# riser-v2.net
KiCad netlist of a schematic drawn in EAGLE
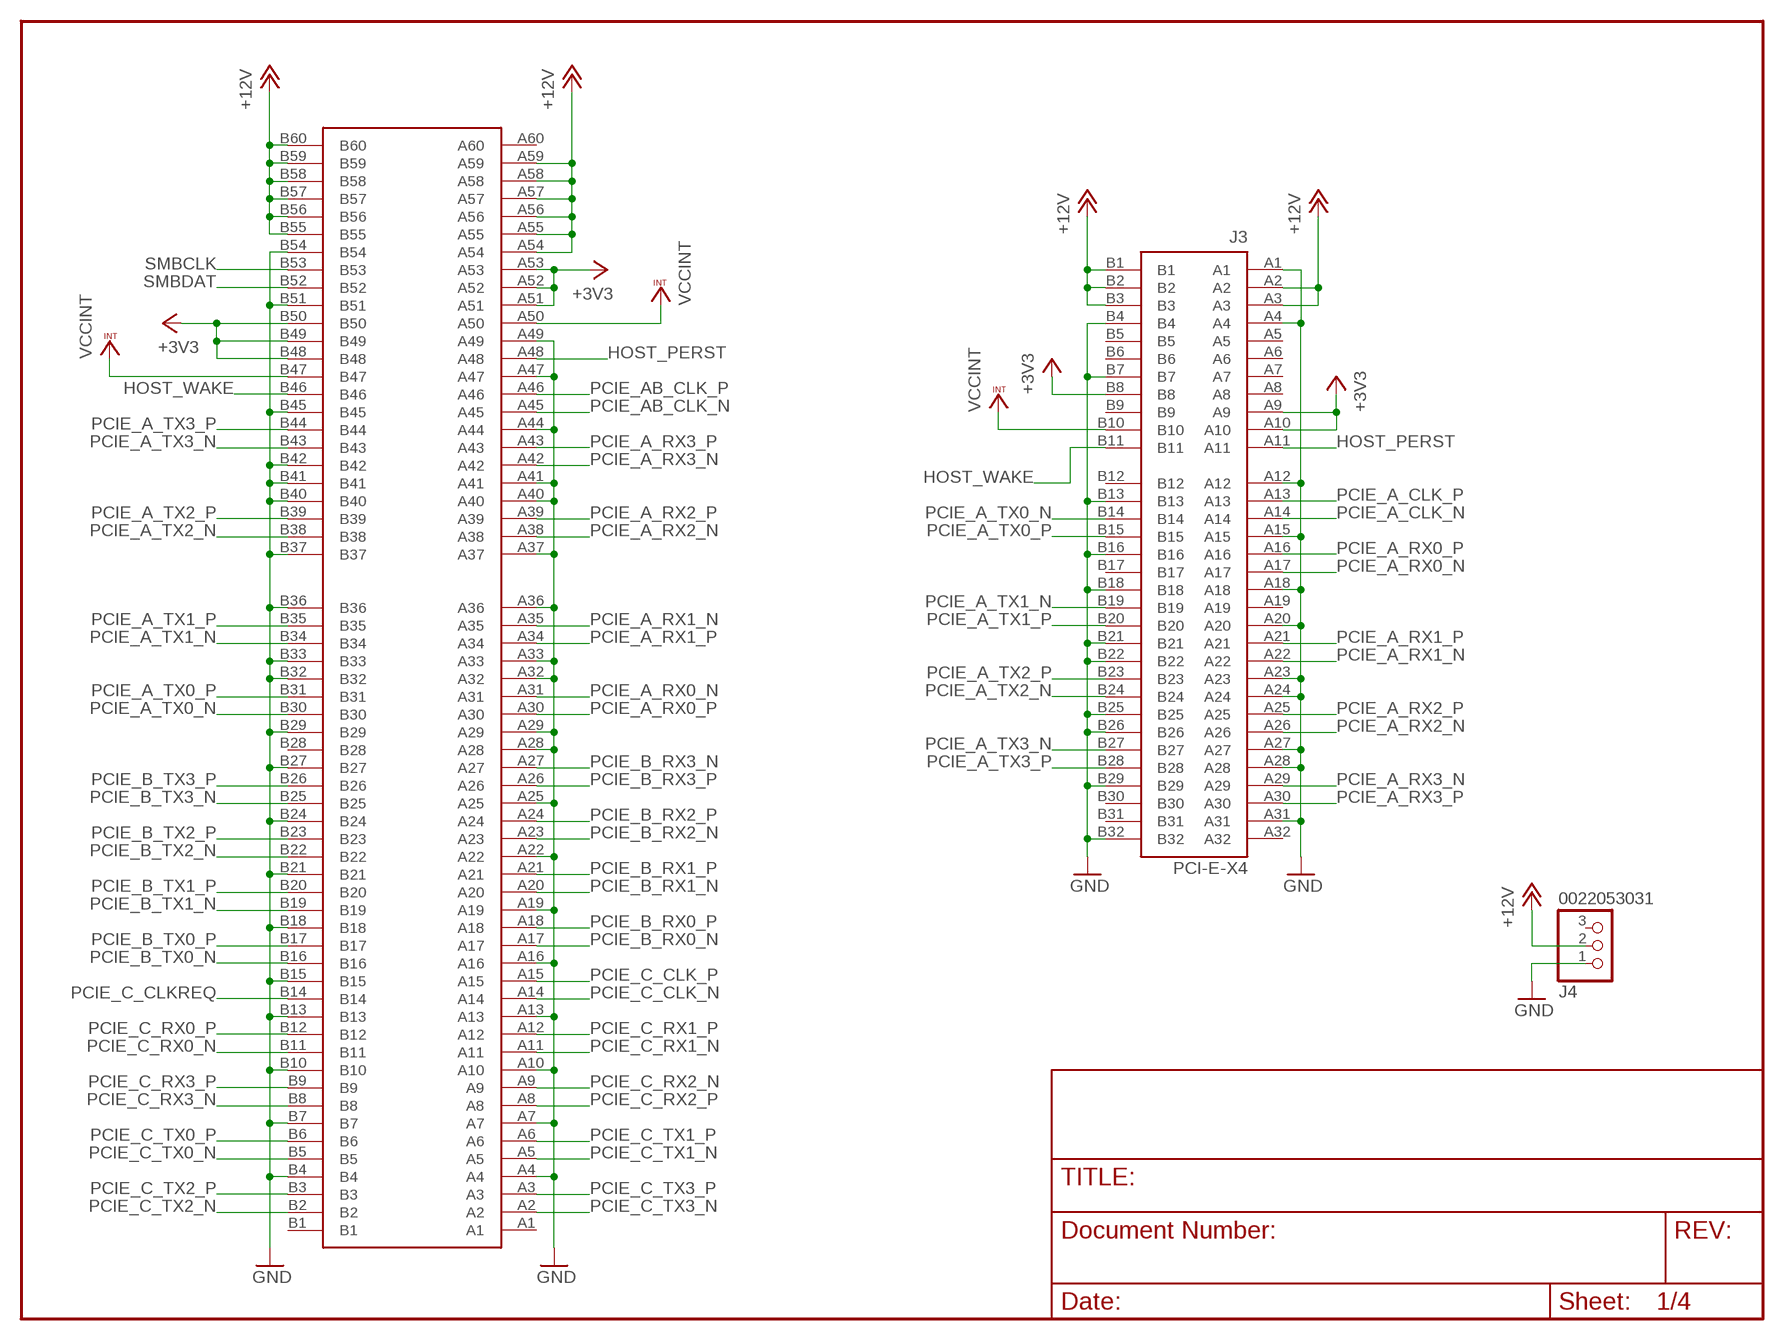
[diagram p0: schematic, sheet 1]
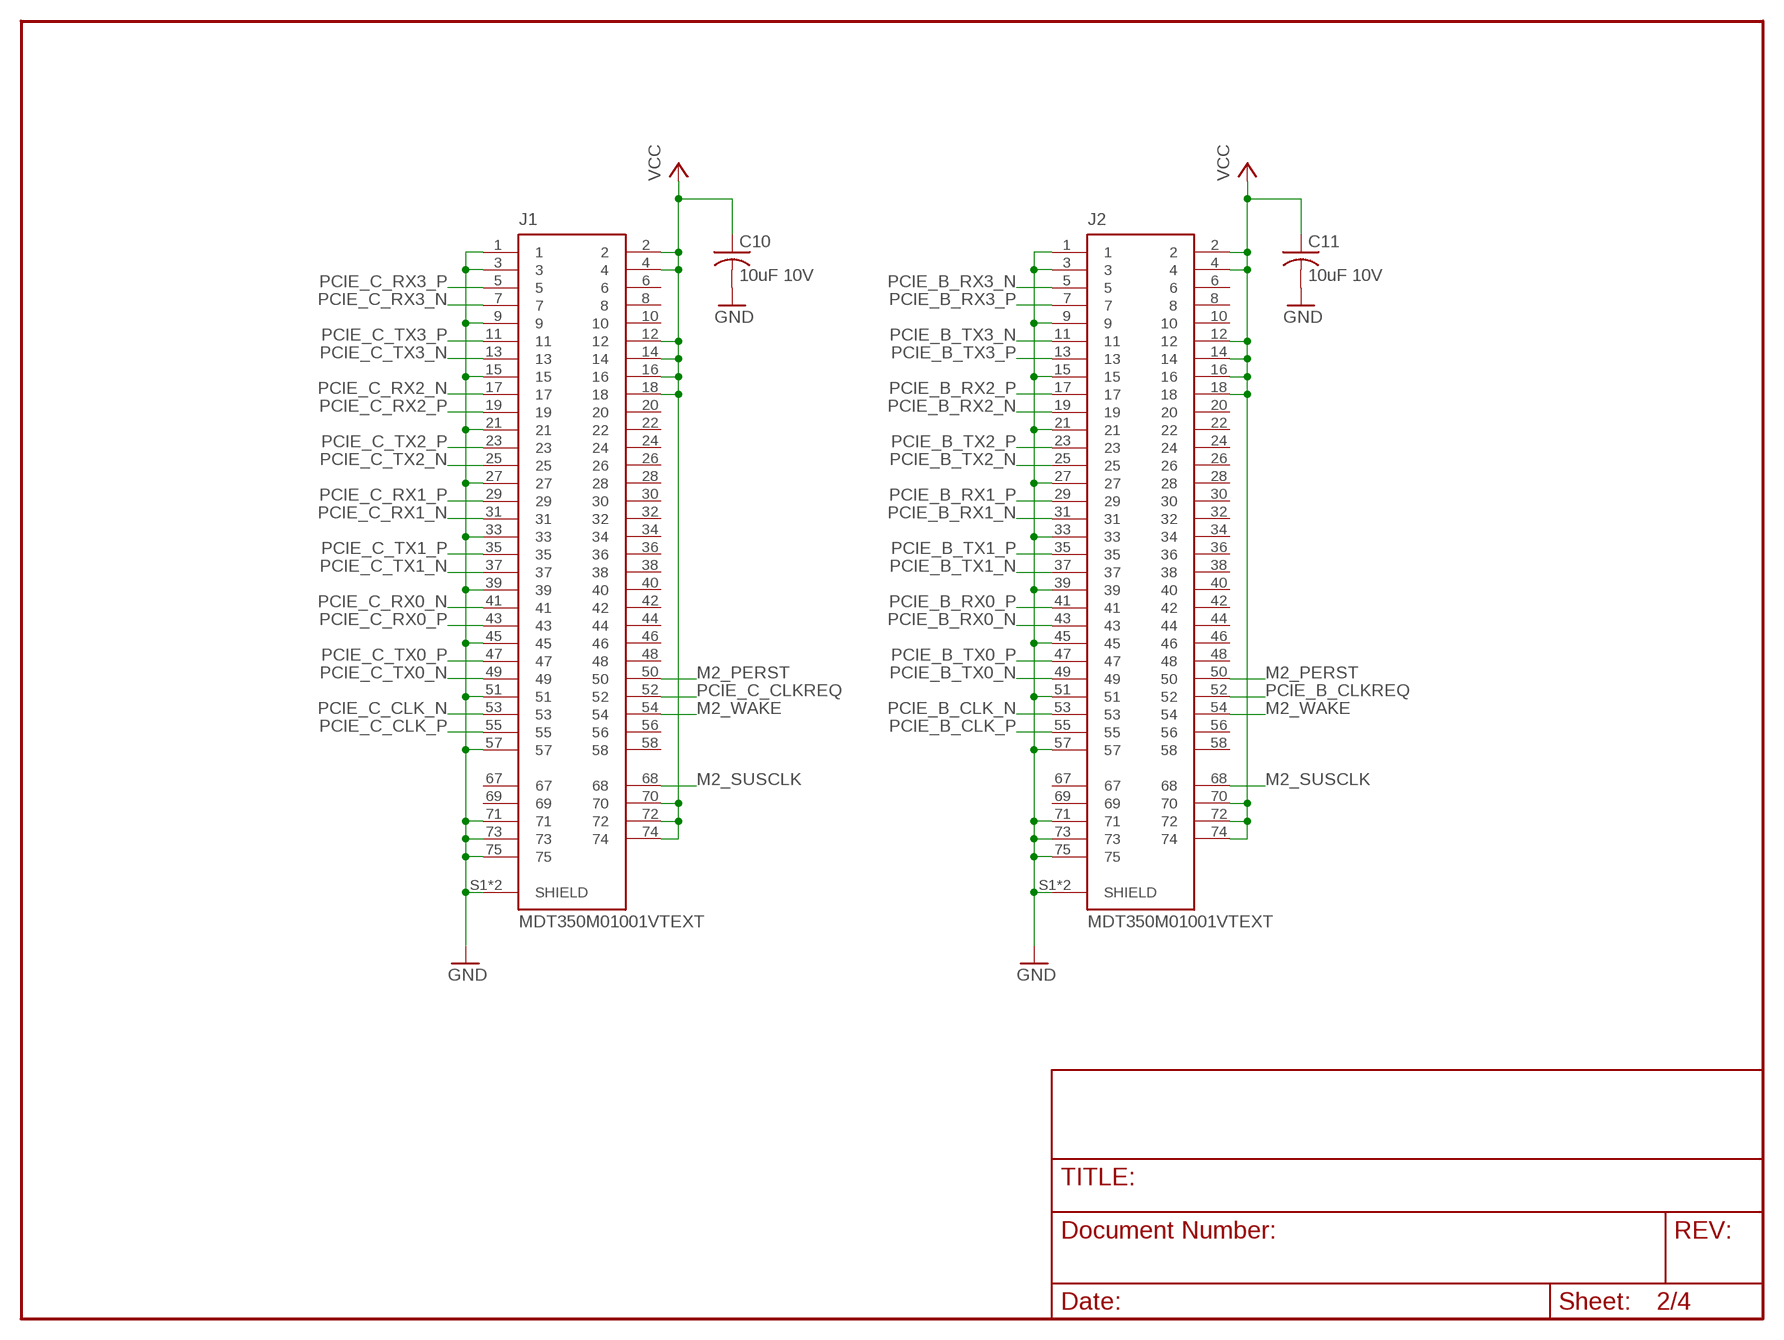
[diagram p1: schematic, sheet 2]
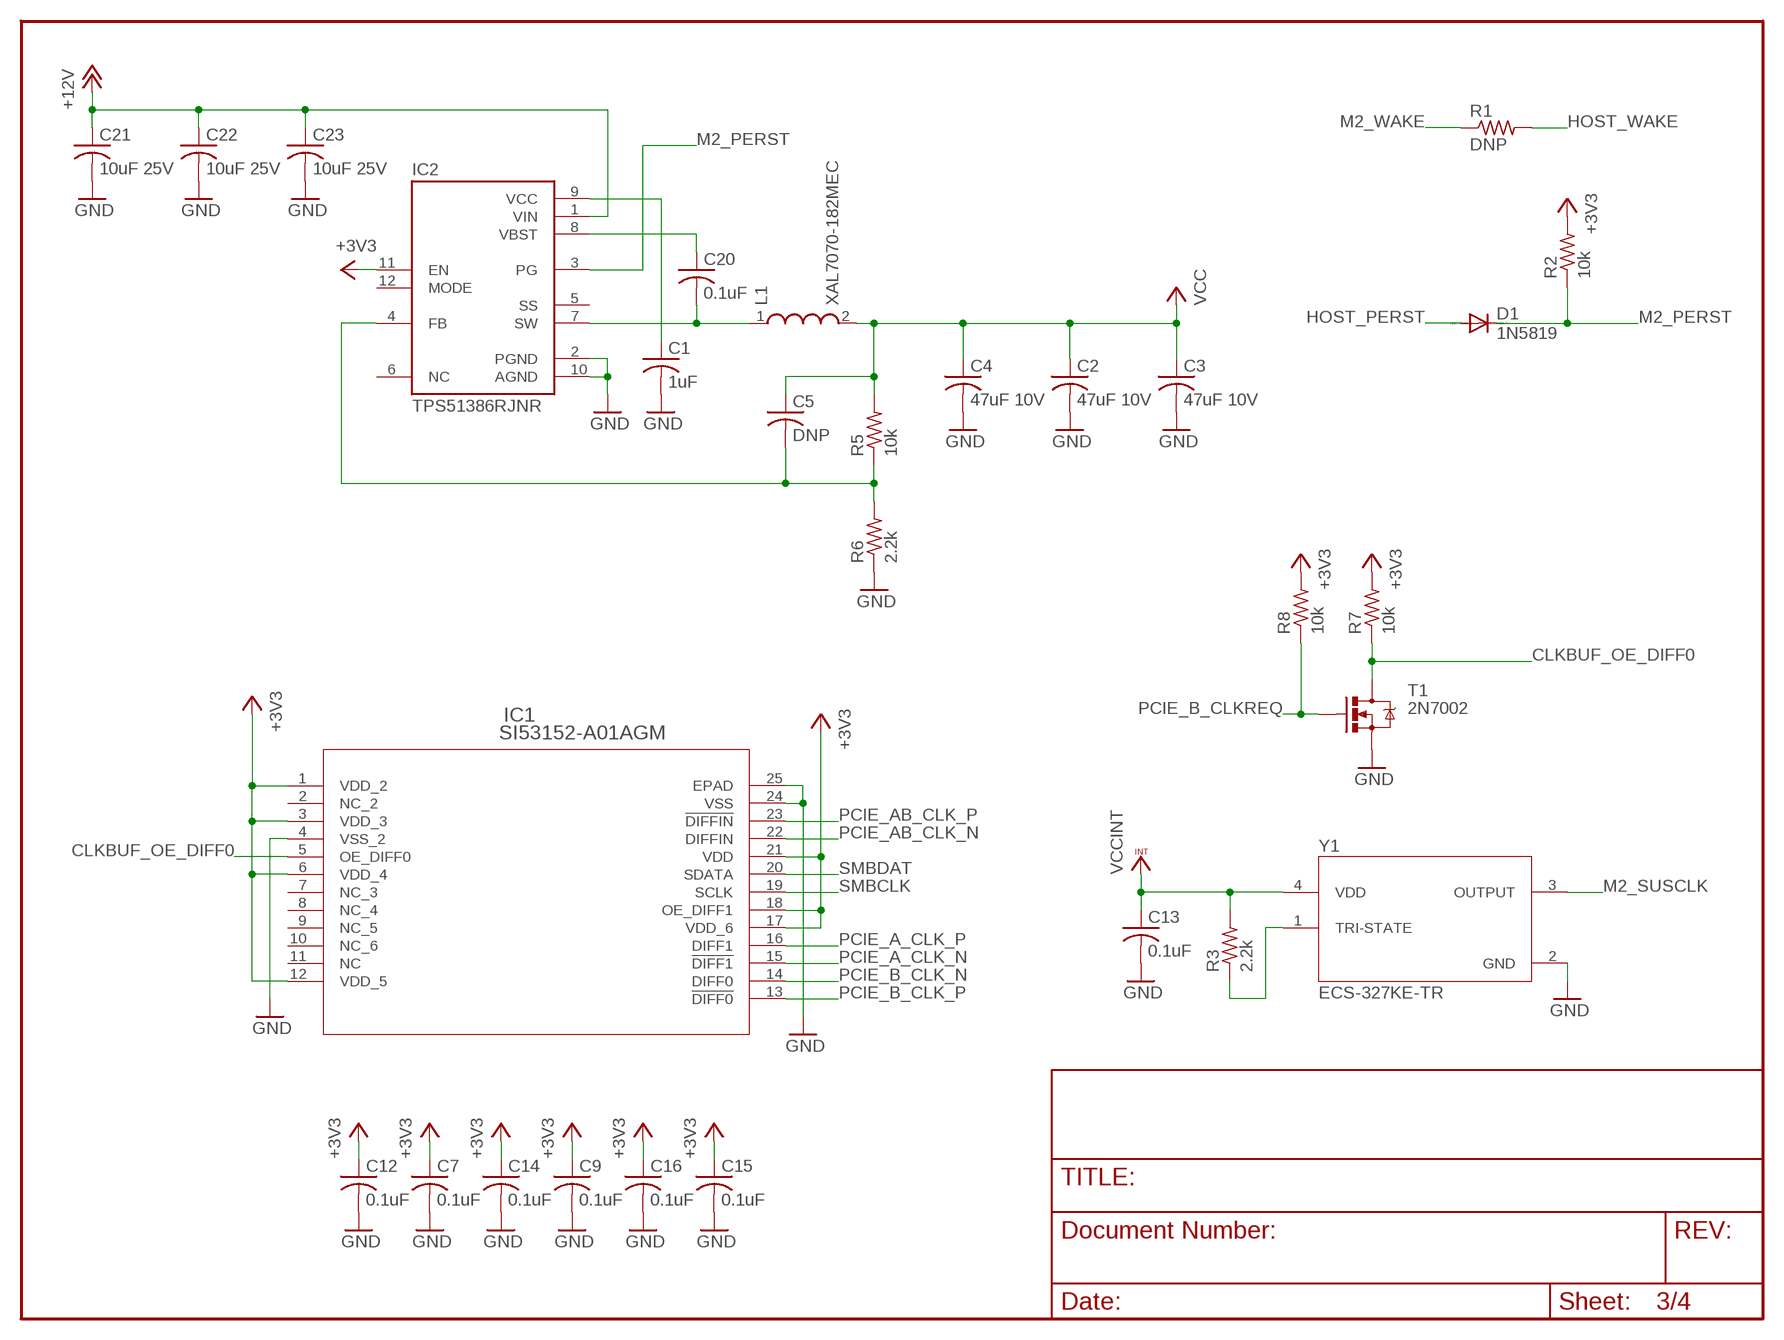
[diagram p2: schematic, sheet 3]
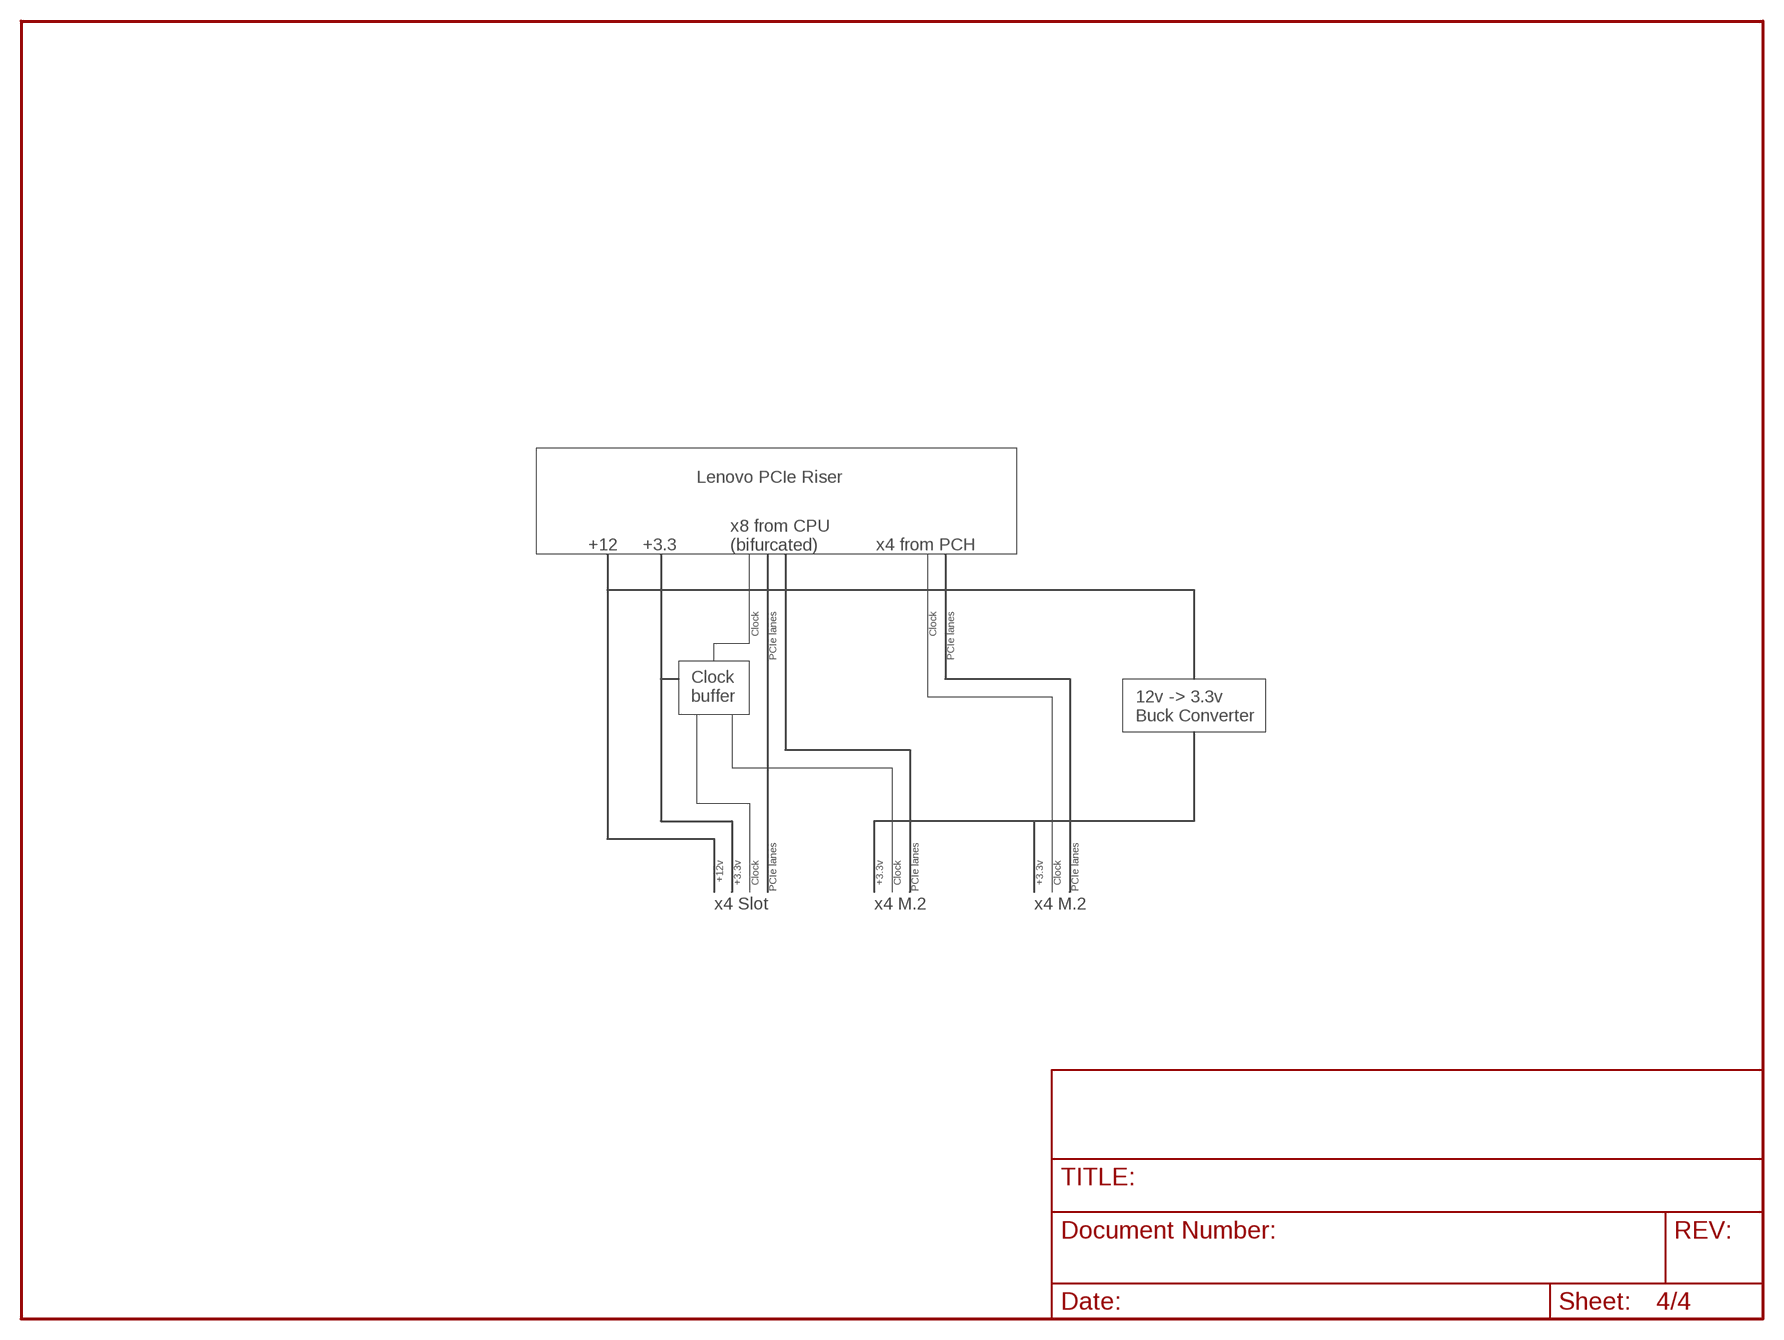
[diagram p3: schematic, sheet 4]

(export (version "E")
  (design (tool "Eeschema 10.0.6"))
  (components
    (comp (ref "C10")
      (value "10uF 10V")
      (footprint "eagle-import:C0603")
      (libsource (lib "eagle-import") (part "C-USC0603"))
    )
    (comp (ref "C11")
      (value "10uF 10V")
      (footprint "eagle-import:C0603")
      (libsource (lib "eagle-import") (part "C-USC0603"))
    )
    (comp (ref "J1")
      (value "MDT350M01001VTEXT")
      (footprint "eagle-import:MDT350M01001VT_EXT")
      (libsource (lib "eagle-import") (part "MDT350M01001VTEXT"))
    )
    (comp (ref "J2")
      (value "MDT350M01001VTEXT")
      (footprint "eagle-import:MDT350M01001VT_EXT")
      (libsource (lib "eagle-import") (part "MDT350M01001VTEXT"))
    )
    (comp (ref "C1")
      (value "1uF")
      (footprint "eagle-import:C0402")
      (libsource (lib "eagle-import") (part "C-USC0402"))
    )
    (comp (ref "C2")
      (value "47uF 10V")
      (footprint "eagle-import:C1206")
      (libsource (lib "eagle-import") (part "resistor_C-USC1206"))
    )
    (comp (ref "C3")
      (value "47uF 10V")
      (footprint "eagle-import:C1206")
      (libsource (lib "eagle-import") (part "resistor_C-USC1206"))
    )
    (comp (ref "C4")
      (value "47uF 10V")
      (footprint "eagle-import:C1206")
      (libsource (lib "eagle-import") (part "resistor_C-USC1206"))
    )
    (comp (ref "C5")
      (value "DNP")
      (footprint "eagle-import:C0402")
      (libsource (lib "eagle-import") (part "C-USC0402"))
    )
    (comp (ref "C7")
      (value "0.1uF")
      (footprint "eagle-import:C0402")
      (libsource (lib "eagle-import") (part "C-USC0402"))
    )
    (comp (ref "C9")
      (value "0.1uF")
      (footprint "eagle-import:C0402")
      (libsource (lib "eagle-import") (part "C-USC0402"))
    )
    (comp (ref "C12")
      (value "0.1uF")
      (footprint "eagle-import:C0402")
      (libsource (lib "eagle-import") (part "C-USC0402"))
    )
    (comp (ref "C13")
      (value "0.1uF")
      (footprint "eagle-import:C0402")
      (libsource (lib "eagle-import") (part "C-USC0402"))
    )
    (comp (ref "C14")
      (value "0.1uF")
      (footprint "eagle-import:C0402")
      (libsource (lib "eagle-import") (part "C-USC0402"))
    )
    (comp (ref "C15")
      (value "0.1uF")
      (footprint "eagle-import:C0402")
      (libsource (lib "eagle-import") (part "C-USC0402"))
    )
    (comp (ref "C16")
      (value "0.1uF")
      (footprint "eagle-import:C0402")
      (libsource (lib "eagle-import") (part "C-USC0402"))
    )
    (comp (ref "C20")
      (value "0.1uF")
      (footprint "eagle-import:C0402")
      (libsource (lib "eagle-import") (part "C-USC0402"))
    )
    (comp (ref "C21")
      (value "10uF 25V")
      (footprint "eagle-import:C1206")
      (libsource (lib "eagle-import") (part "resistor_C-USC1206"))
    )
    (comp (ref "C22")
      (value "10uF 25V")
      (footprint "eagle-import:C1206")
      (libsource (lib "eagle-import") (part "resistor_C-USC1206"))
    )
    (comp (ref "C23")
      (value "10uF 25V")
      (footprint "eagle-import:C1206")
      (libsource (lib "eagle-import") (part "resistor_C-USC1206"))
    )
    (comp (ref "D1")
      (value "1N5819")
      (footprint "eagle-import:SOD323-R")
      (libsource (lib "eagle-import") (part "DIODE-SOD323-R"))
    )
    (comp (ref "IC1")
      (value "SI53152-A01AGM")
      (footprint "eagle-import:QFN24_4X4_SIL")
      (fields (field (name "COPYRIGHT") "Copyright (C) 2024 Ultra Librarian. All rights reserved."))
      (libsource (lib "eagle-import") (part "SI53152-A01AGM"))
    )
    (comp (ref "IC2")
      (value "TPS51386RJNR")
      (footprint "eagle-import:VREG_TPS51386RJNR")
      (fields (field (name "MF") "Texas Instruments"))
      (libsource (lib "eagle-import") (part "TPS51386RJNR"))
    )
    (comp (ref "L1")
      (value "XAL7070-182MEC")
      (footprint "eagle-import:DFN750X725X700-2N")
      (fields (field (name "MF") "Coilcraft") (field (name "MP") "XAL7070-332MEB"))
      (libsource (lib "eagle-import") (part "XAL7070-332MEB"))
    )
    (comp (ref "R1")
      (value "DNP")
      (footprint "eagle-import:R0402")
      (libsource (lib "eagle-import") (part "R-US_R0402"))
    )
    (comp (ref "R2")
      (value "10k")
      (footprint "eagle-import:R0402")
      (libsource (lib "eagle-import") (part "R-US_R0402"))
    )
    (comp (ref "R3")
      (value "2.2k")
      (footprint "eagle-import:R0402")
      (libsource (lib "eagle-import") (part "R-US_R0402"))
    )
    (comp (ref "R5")
      (value "10k")
      (footprint "eagle-import:R0402")
      (libsource (lib "eagle-import") (part "R-US_R0402"))
    )
    (comp (ref "R6")
      (value "2.2k")
      (footprint "eagle-import:R0402")
      (libsource (lib "eagle-import") (part "R-US_R0402"))
    )
    (comp (ref "R7")
      (value "10k")
      (footprint "eagle-import:R0402")
      (libsource (lib "eagle-import") (part "R-US_R0402"))
    )
    (comp (ref "R8")
      (value "10k")
      (footprint "eagle-import:R0402")
      (libsource (lib "eagle-import") (part "R-US_R0402"))
    )
    (comp (ref "T1")
      (value "2N7002")
      (footprint "eagle-import:SOT23-3")
      (libsource (lib "eagle-import") (part "MOSFET-NCHANNELSMD"))
    )
    (comp (ref "Y1")
      (value "ECS-327KE-TR")
      (footprint "eagle-import:OSC_ECS-327KE-TR")
      (fields (field (name "MF") "ECS Inc."))
      (libsource (lib "eagle-import") (part "ECS-327KE-TR"))
    )
    (comp (ref "J3")
      (value "PCI-E-X4")
      (footprint "eagle-import:PCI-E-X4")
      (libsource (lib "eagle-import") (part "PCI-E-X4"))
    )
    (comp (ref "J4")
      (value "0022053031")
      (footprint "eagle-import:1X03")
      (libsource (lib "eagle-import") (part "PINHD-1X3"))
    )
    (comp (ref "JP1")
      (value "ADDR0262")
      (footprint "eagle-import:ADDR0262-EDGE")
      (libsource (lib "eagle-import") (part "ADDR0262"))
    )
  )
  (nets
    (net (code "1") (name "+3V3") (class "Default")
      (node (ref "C12") (pin "1") (pinfunction "1_1") (pintype "passive"))
      (node (ref "C14") (pin "1") (pinfunction "1_1") (pintype "passive"))
      (node (ref "C15") (pin "1") (pinfunction "1_1") (pintype "passive"))
      (node (ref "C16") (pin "1") (pinfunction "1_1") (pintype "passive"))
      (node (ref "C7") (pin "1") (pinfunction "1_1") (pintype "passive"))
      (node (ref "C9") (pin "1") (pinfunction "1_1") (pintype "passive"))
      (node (ref "IC1") (pin "1") (pinfunction "VDD_2_1") (pintype "power_in"))
      (node (ref "IC1") (pin "12") (pinfunction "VDD_5_12") (pintype "power_in"))
      (node (ref "IC1") (pin "17") (pinfunction "VDD_6_17") (pintype "power_in"))
      (node (ref "IC1") (pin "18") (pinfunction "OE_DIFF1_18") (pintype "input"))
      (node (ref "IC1") (pin "21") (pinfunction "VDD_21") (pintype "power_in"))
      (node (ref "IC1") (pin "3") (pinfunction "VDD_3_3") (pintype "power_in"))
      (node (ref "IC1") (pin "6") (pinfunction "VDD_4_6") (pintype "power_in"))
      (node (ref "IC2") (pin "11") (pinfunction "EN_11") (pintype "input"))
      (node (ref "J3") (pin "A10") (pinfunction "A10_A10") (pintype "passive"))
      (node (ref "J3") (pin "A9") (pinfunction "A9_A9") (pintype "passive"))
      (node (ref "J3") (pin "B8") (pinfunction "B8_B8") (pintype "passive"))
      (node (ref "JP1") (pin "A51") (pinfunction "A51_A51") (pintype "bidirectional"))
      (node (ref "JP1") (pin "A52") (pinfunction "A52_A52") (pintype "bidirectional"))
      (node (ref "JP1") (pin "A53") (pinfunction "A53_A53") (pintype "bidirectional"))
      (node (ref "JP1") (pin "B48") (pinfunction "B48_B48") (pintype "bidirectional"))
      (node (ref "JP1") (pin "B49") (pinfunction "B49_B49") (pintype "bidirectional"))
      (node (ref "JP1") (pin "B50") (pinfunction "B50_B50") (pintype "bidirectional"))
      (node (ref "R2") (pin "2") (pinfunction "2_2") (pintype "passive"))
      (node (ref "R7") (pin "2") (pinfunction "2_2") (pintype "passive"))
      (node (ref "R8") (pin "2") (pinfunction "2_2") (pintype "passive"))
    )
    (net (code "2") (name "+12V") (class "Default")
      (node (ref "C21") (pin "1") (pinfunction "1_1") (pintype "passive"))
      (node (ref "C22") (pin "1") (pinfunction "1_1") (pintype "passive"))
      (node (ref "C23") (pin "1") (pinfunction "1_1") (pintype "passive"))
      (node (ref "IC2") (pin "1") (pinfunction "VIN_1") (pintype "power_in"))
      (node (ref "J3") (pin "A2") (pinfunction "A2_A2") (pintype "passive"))
      (node (ref "J3") (pin "A3") (pinfunction "A3_A3") (pintype "passive"))
      (node (ref "J3") (pin "B1") (pinfunction "B1_B1") (pintype "passive"))
      (node (ref "J3") (pin "B2") (pinfunction "B2_B2") (pintype "passive"))
      (node (ref "J3") (pin "B3") (pinfunction "B3_B3") (pintype "passive"))
      (node (ref "J4") (pin "2") (pinfunction "2_2") (pintype "passive"))
      (node (ref "JP1") (pin "A54") (pinfunction "A54_A54") (pintype "bidirectional"))
      (node (ref "JP1") (pin "A55") (pinfunction "A55_A55") (pintype "bidirectional"))
      (node (ref "JP1") (pin "A56") (pinfunction "A56_A56") (pintype "bidirectional"))
      (node (ref "JP1") (pin "A57") (pinfunction "A57_A57") (pintype "bidirectional"))
      (node (ref "JP1") (pin "A58") (pinfunction "A58_A58") (pintype "bidirectional"))
      (node (ref "JP1") (pin "A59") (pinfunction "A59_A59") (pintype "bidirectional"))
      (node (ref "JP1") (pin "B55") (pinfunction "B55_B55") (pintype "bidirectional"))
      (node (ref "JP1") (pin "B56") (pinfunction "B56_B56") (pintype "bidirectional"))
      (node (ref "JP1") (pin "B57") (pinfunction "B57_B57") (pintype "bidirectional"))
      (node (ref "JP1") (pin "B58") (pinfunction "B58_B58") (pintype "bidirectional"))
      (node (ref "JP1") (pin "B59") (pinfunction "B59_B59") (pintype "bidirectional"))
      (node (ref "JP1") (pin "B60") (pinfunction "B60_B60") (pintype "bidirectional"))
    )
    (net (code "3") (name "CLKBUF_OE_DIFF0") (class "Default")
      (node (ref "IC1") (pin "5") (pinfunction "OE_DIFF0_5") (pintype "input"))
      (node (ref "R7") (pin "1") (pinfunction "1_1") (pintype "passive"))
      (node (ref "T1") (pin "3") (pinfunction "D_3") (pintype "passive"))
    )
    (net (code "4") (name "GND") (class "Default")
      (node (ref "C1") (pin "2") (pinfunction "2_2") (pintype "passive"))
      (node (ref "C10") (pin "2") (pinfunction "2_2") (pintype "passive"))
      (node (ref "C11") (pin "2") (pinfunction "2_2") (pintype "passive"))
      (node (ref "C12") (pin "2") (pinfunction "2_2") (pintype "passive"))
      (node (ref "C13") (pin "2") (pinfunction "2_2") (pintype "passive"))
      (node (ref "C14") (pin "2") (pinfunction "2_2") (pintype "passive"))
      (node (ref "C15") (pin "2") (pinfunction "2_2") (pintype "passive"))
      (node (ref "C16") (pin "2") (pinfunction "2_2") (pintype "passive"))
      (node (ref "C2") (pin "2") (pinfunction "2_2") (pintype "passive"))
      (node (ref "C21") (pin "2") (pinfunction "2_2") (pintype "passive"))
      (node (ref "C22") (pin "2") (pinfunction "2_2") (pintype "passive"))
      (node (ref "C23") (pin "2") (pinfunction "2_2") (pintype "passive"))
      (node (ref "C3") (pin "2") (pinfunction "2_2") (pintype "passive"))
      (node (ref "C4") (pin "2") (pinfunction "2_2") (pintype "passive"))
      (node (ref "C7") (pin "2") (pinfunction "2_2") (pintype "passive"))
      (node (ref "C9") (pin "2") (pinfunction "2_2") (pintype "passive"))
      (node (ref "IC1") (pin "24") (pinfunction "VSS_24") (pintype "power_in"))
      (node (ref "IC1") (pin "25") (pinfunction "EPAD_25") (pintype "passive"))
      (node (ref "IC1") (pin "4") (pinfunction "VSS_2_4") (pintype "power_in"))
      (node (ref "IC2") (pin "10") (pinfunction "AGND_10") (pintype "power_in"))
      (node (ref "IC2") (pin "2") (pinfunction "PGND_2") (pintype "power_in"))
      (node (ref "J1") (pin "1") (pinfunction "1_1") (pintype "passive"))
      (node (ref "J1") (pin "15") (pinfunction "15_15") (pintype "passive"))
      (node (ref "J1") (pin "21") (pinfunction "21_21") (pintype "passive"))
      (node (ref "J1") (pin "27") (pinfunction "27_27") (pintype "passive"))
      (node (ref "J1") (pin "3") (pinfunction "3_3") (pintype "passive"))
      (node (ref "J1") (pin "33") (pinfunction "33_33") (pintype "passive"))
      (node (ref "J1") (pin "39") (pinfunction "39_39") (pintype "passive"))
      (node (ref "J1") (pin "45") (pinfunction "45_45") (pintype "passive"))
      (node (ref "J1") (pin "51") (pinfunction "51_51") (pintype "passive"))
      (node (ref "J1") (pin "57") (pinfunction "57_57") (pintype "passive"))
      (node (ref "J1") (pin "71") (pinfunction "71_71") (pintype "passive"))
      (node (ref "J1") (pin "73") (pinfunction "73_73") (pintype "passive"))
      (node (ref "J1") (pin "75") (pinfunction "75_75") (pintype "passive"))
      (node (ref "J1") (pin "9") (pinfunction "9_9") (pintype "passive"))
      (node (ref "J1") (pin "S1") (pinfunction "SHIELD_S1") (pintype "passive"))
      (node (ref "J1") (pin "S2") (pinfunction "SHIELD_S2") (pintype "passive"))
      (node (ref "J2") (pin "1") (pinfunction "1_1") (pintype "passive"))
      (node (ref "J2") (pin "15") (pinfunction "15_15") (pintype "passive"))
      (node (ref "J2") (pin "21") (pinfunction "21_21") (pintype "passive"))
      (node (ref "J2") (pin "27") (pinfunction "27_27") (pintype "passive"))
      (node (ref "J2") (pin "3") (pinfunction "3_3") (pintype "passive"))
      (node (ref "J2") (pin "33") (pinfunction "33_33") (pintype "passive"))
      (node (ref "J2") (pin "39") (pinfunction "39_39") (pintype "passive"))
      (node (ref "J2") (pin "45") (pinfunction "45_45") (pintype "passive"))
      (node (ref "J2") (pin "51") (pinfunction "51_51") (pintype "passive"))
      (node (ref "J2") (pin "57") (pinfunction "57_57") (pintype "passive"))
      (node (ref "J2") (pin "71") (pinfunction "71_71") (pintype "passive"))
      (node (ref "J2") (pin "73") (pinfunction "73_73") (pintype "passive"))
      (node (ref "J2") (pin "75") (pinfunction "75_75") (pintype "passive"))
      (node (ref "J2") (pin "9") (pinfunction "9_9") (pintype "passive"))
      (node (ref "J2") (pin "S1") (pinfunction "SHIELD_S1") (pintype "passive"))
      (node (ref "J2") (pin "S2") (pinfunction "SHIELD_S2") (pintype "passive"))
      (node (ref "J3") (pin "A1") (pinfunction "A1_A1") (pintype "passive"))
      (node (ref "J3") (pin "A12") (pinfunction "A12_A12") (pintype "passive"))
      (node (ref "J3") (pin "A15") (pinfunction "A15_A15") (pintype "passive"))
      (node (ref "J3") (pin "A18") (pinfunction "A18_A18") (pintype "passive"))
      (node (ref "J3") (pin "A20") (pinfunction "A20_A20") (pintype "passive"))
      (node (ref "J3") (pin "A23") (pinfunction "A23_A23") (pintype "passive"))
      (node (ref "J3") (pin "A24") (pinfunction "A24_A24") (pintype "passive"))
      (node (ref "J3") (pin "A27") (pinfunction "A27_A27") (pintype "passive"))
      (node (ref "J3") (pin "A28") (pinfunction "A28_A28") (pintype "passive"))
      (node (ref "J3") (pin "A31") (pinfunction "A31_A31") (pintype "passive"))
      (node (ref "J3") (pin "A4") (pinfunction "A4_A4") (pintype "passive"))
      (node (ref "J3") (pin "B13") (pinfunction "B13_B13") (pintype "passive"))
      (node (ref "J3") (pin "B16") (pinfunction "B16_B16") (pintype "passive"))
      (node (ref "J3") (pin "B18") (pinfunction "B18_B18") (pintype "passive"))
      (node (ref "J3") (pin "B21") (pinfunction "B21_B21") (pintype "passive"))
      (node (ref "J3") (pin "B22") (pinfunction "B22_B22") (pintype "passive"))
      (node (ref "J3") (pin "B25") (pinfunction "B25_B25") (pintype "passive"))
      (node (ref "J3") (pin "B26") (pinfunction "B26_B26") (pintype "passive"))
      (node (ref "J3") (pin "B29") (pinfunction "B29_B29") (pintype "passive"))
      (node (ref "J3") (pin "B32") (pinfunction "B32_B32") (pintype "passive"))
      (node (ref "J3") (pin "B4") (pinfunction "B4_B4") (pintype "passive"))
      (node (ref "J3") (pin "B7") (pinfunction "B7_B7") (pintype "passive"))
      (node (ref "J4") (pin "1") (pinfunction "1_1") (pintype "passive"))
      (node (ref "JP1") (pin "A10") (pinfunction "A10_A10") (pintype "bidirectional"))
      (node (ref "JP1") (pin "A13") (pinfunction "A13_A13") (pintype "bidirectional"))
      (node (ref "JP1") (pin "A16") (pinfunction "A16_A16") (pintype "bidirectional"))
      (node (ref "JP1") (pin "A19") (pinfunction "A19_A19") (pintype "bidirectional"))
      (node (ref "JP1") (pin "A22") (pinfunction "A22_A22") (pintype "bidirectional"))
      (node (ref "JP1") (pin "A25") (pinfunction "A25_A25") (pintype "bidirectional"))
      (node (ref "JP1") (pin "A28") (pinfunction "A28_A28") (pintype "bidirectional"))
      (node (ref "JP1") (pin "A29") (pinfunction "A29_A29") (pintype "bidirectional"))
      (node (ref "JP1") (pin "A32") (pinfunction "A32_A32") (pintype "bidirectional"))
      (node (ref "JP1") (pin "A33") (pinfunction "A33_A33") (pintype "bidirectional"))
      (node (ref "JP1") (pin "A36") (pinfunction "A36_A36") (pintype "bidirectional"))
      (node (ref "JP1") (pin "A37") (pinfunction "A37_A37") (pintype "bidirectional"))
      (node (ref "JP1") (pin "A4") (pinfunction "A4_A4") (pintype "bidirectional"))
      (node (ref "JP1") (pin "A40") (pinfunction "A40_A40") (pintype "bidirectional"))
      (node (ref "JP1") (pin "A41") (pinfunction "A41_A41") (pintype "bidirectional"))
      (node (ref "JP1") (pin "A44") (pinfunction "A44_A44") (pintype "bidirectional"))
      (node (ref "JP1") (pin "A47") (pinfunction "A47_A47") (pintype "bidirectional"))
      (node (ref "JP1") (pin "A49") (pinfunction "A49_A49") (pintype "bidirectional"))
      (node (ref "JP1") (pin "A7") (pinfunction "A7_A7") (pintype "bidirectional"))
      (node (ref "JP1") (pin "B10") (pinfunction "B10_B10") (pintype "bidirectional"))
      (node (ref "JP1") (pin "B13") (pinfunction "B13_B13") (pintype "bidirectional"))
      (node (ref "JP1") (pin "B15") (pinfunction "B15_B15") (pintype "bidirectional"))
      (node (ref "JP1") (pin "B18") (pinfunction "B18_B18") (pintype "bidirectional"))
      (node (ref "JP1") (pin "B21") (pinfunction "B21_B21") (pintype "bidirectional"))
      (node (ref "JP1") (pin "B24") (pinfunction "B24_B24") (pintype "bidirectional"))
      (node (ref "JP1") (pin "B27") (pinfunction "B27_B27") (pintype "bidirectional"))
      (node (ref "JP1") (pin "B29") (pinfunction "B29_B29") (pintype "bidirectional"))
      (node (ref "JP1") (pin "B32") (pinfunction "B32_B32") (pintype "bidirectional"))
      (node (ref "JP1") (pin "B33") (pinfunction "B33_B33") (pintype "bidirectional"))
      (node (ref "JP1") (pin "B36") (pinfunction "B36_B36") (pintype "bidirectional"))
      (node (ref "JP1") (pin "B37") (pinfunction "B37_B37") (pintype "bidirectional"))
      (node (ref "JP1") (pin "B4") (pinfunction "B4_B4") (pintype "bidirectional"))
      (node (ref "JP1") (pin "B40") (pinfunction "B40_B40") (pintype "bidirectional"))
      (node (ref "JP1") (pin "B41") (pinfunction "B41_B41") (pintype "bidirectional"))
      (node (ref "JP1") (pin "B42") (pinfunction "B42_B42") (pintype "bidirectional"))
      (node (ref "JP1") (pin "B45") (pinfunction "B45_B45") (pintype "bidirectional"))
      (node (ref "JP1") (pin "B51") (pinfunction "B51_B51") (pintype "bidirectional"))
      (node (ref "JP1") (pin "B54") (pinfunction "B54_B54") (pintype "bidirectional"))
      (node (ref "JP1") (pin "B7") (pinfunction "B7_B7") (pintype "bidirectional"))
      (node (ref "R6") (pin "1") (pinfunction "1_1") (pintype "passive"))
      (node (ref "T1") (pin "2") (pinfunction "S_2") (pintype "passive"))
      (node (ref "Y1") (pin "2") (pinfunction "GND_2") (pintype "power_in"))
    )
    (net (code "5") (name "HOST_PERST") (class "Default")
      (node (ref "D1") (pin "A") (pinfunction "A_A") (pintype "passive"))
      (node (ref "J3") (pin "A11") (pinfunction "A11_A11") (pintype "passive"))
      (node (ref "JP1") (pin "A48") (pinfunction "A48_A48") (pintype "bidirectional"))
    )
    (net (code "6") (name "HOST_WAKE") (class "Default")
      (node (ref "J3") (pin "B11") (pinfunction "B11_B11") (pintype "passive"))
      (node (ref "JP1") (pin "B46") (pinfunction "B46_B46") (pintype "bidirectional"))
      (node (ref "R1") (pin "2") (pinfunction "2_2") (pintype "passive"))
    )
    (net (code "7") (name "M2_PERST") (class "Default")
      (node (ref "D1") (pin "C") (pinfunction "C_C") (pintype "passive"))
      (node (ref "IC2") (pin "3") (pinfunction "PG_3") (pintype "output"))
      (node (ref "J1") (pin "50") (pinfunction "50_50") (pintype "passive"))
      (node (ref "J2") (pin "50") (pinfunction "50_50") (pintype "passive"))
      (node (ref "R2") (pin "1") (pinfunction "1_1") (pintype "passive"))
    )
    (net (code "8") (name "M2_SUSCLK") (class "Default")
      (node (ref "J1") (pin "68") (pinfunction "68_68") (pintype "passive"))
      (node (ref "J2") (pin "68") (pinfunction "68_68") (pintype "passive"))
      (node (ref "Y1") (pin "3") (pinfunction "OUTPUT_3") (pintype "output"))
    )
    (net (code "9") (name "M2_WAKE") (class "Default")
      (node (ref "J1") (pin "54") (pinfunction "54_54") (pintype "passive"))
      (node (ref "J2") (pin "54") (pinfunction "54_54") (pintype "passive"))
      (node (ref "R1") (pin "1") (pinfunction "1_1") (pintype "passive"))
    )
    (net (code "10") (name "Net-(IC2-FB)") (class "Default")
      (node (ref "C5") (pin "2") (pinfunction "2_2") (pintype "passive"))
      (node (ref "IC2") (pin "4") (pinfunction "FB_4") (pintype "input"))
      (node (ref "R5") (pin "1") (pinfunction "1_1") (pintype "passive"))
      (node (ref "R6") (pin "2") (pinfunction "2_2") (pintype "passive"))
    )
    (net (code "11") (name "Net-(IC2-SW)") (class "Default")
      (node (ref "C20") (pin "2") (pinfunction "2_2") (pintype "passive"))
      (node (ref "IC2") (pin "7") (pinfunction "SW_7") (pintype "output"))
      (node (ref "L1") (pin "1") (pinfunction "1_1") (pintype "passive"))
    )
    (net (code "12") (name "Net-(IC2-VBST)") (class "Default")
      (node (ref "C20") (pin "1") (pinfunction "1_1") (pintype "passive"))
      (node (ref "IC2") (pin "8") (pinfunction "VBST_8") (pintype "power_in"))
    )
    (net (code "13") (name "Net-(IC2-VCC)") (class "Default")
      (node (ref "C1") (pin "1") (pinfunction "1_1") (pintype "passive"))
      (node (ref "IC2") (pin "9") (pinfunction "VCC_9") (pintype "power_in"))
    )
    (net (code "14") (name "Net-(Y1-TRI-STATE)") (class "Default")
      (node (ref "R3") (pin "1") (pinfunction "1_1") (pintype "passive"))
      (node (ref "Y1") (pin "1") (pinfunction "TRI-STATE_1") (pintype "input"))
    )
    (net (code "15") (name "PCIE_AB_CLK_N") (class "Default")
      (node (ref "IC1") (pin "22") (pinfunction "DIFFIN_22") (pintype "input"))
      (node (ref "JP1") (pin "A45") (pinfunction "A45_A45") (pintype "bidirectional"))
    )
    (net (code "16") (name "PCIE_AB_CLK_P") (class "Default")
      (node (ref "IC1") (pin "23") (pinfunction "~{DIFFIN}_23") (pintype "input"))
      (node (ref "JP1") (pin "A46") (pinfunction "A46_A46") (pintype "bidirectional"))
    )
    (net (code "17") (name "PCIE_A_CLK_N") (class "Default")
      (node (ref "IC1") (pin "15") (pinfunction "~{DIFF1}_15") (pintype "output"))
      (node (ref "J3") (pin "A14") (pinfunction "A14_A14") (pintype "passive"))
    )
    (net (code "18") (name "PCIE_A_CLK_P") (class "Default")
      (node (ref "IC1") (pin "16") (pinfunction "DIFF1_16") (pintype "output"))
      (node (ref "J3") (pin "A13") (pinfunction "A13_A13") (pintype "passive"))
    )
    (net (code "19") (name "PCIE_A_RX0_N") (class "Default")
      (node (ref "J3") (pin "A17") (pinfunction "A17_A17") (pintype "passive"))
      (node (ref "JP1") (pin "A31") (pinfunction "A31_A31") (pintype "bidirectional"))
    )
    (net (code "20") (name "PCIE_A_RX0_P") (class "Default")
      (node (ref "J3") (pin "A16") (pinfunction "A16_A16") (pintype "passive"))
      (node (ref "JP1") (pin "A30") (pinfunction "A30_A30") (pintype "bidirectional"))
    )
    (net (code "21") (name "PCIE_A_RX1_N") (class "Default")
      (node (ref "J3") (pin "A22") (pinfunction "A22_A22") (pintype "passive"))
      (node (ref "JP1") (pin "A35") (pinfunction "A35_A35") (pintype "bidirectional"))
    )
    (net (code "22") (name "PCIE_A_RX1_P") (class "Default")
      (node (ref "J3") (pin "A21") (pinfunction "A21_A21") (pintype "passive"))
      (node (ref "JP1") (pin "A34") (pinfunction "A34_A34") (pintype "bidirectional"))
    )
    (net (code "23") (name "PCIE_A_RX2_N") (class "Default")
      (node (ref "J3") (pin "A26") (pinfunction "A26_A26") (pintype "passive"))
      (node (ref "JP1") (pin "A38") (pinfunction "A38_A38") (pintype "bidirectional"))
    )
    (net (code "24") (name "PCIE_A_RX2_P") (class "Default")
      (node (ref "J3") (pin "A25") (pinfunction "A25_A25") (pintype "passive"))
      (node (ref "JP1") (pin "A39") (pinfunction "A39_A39") (pintype "bidirectional"))
    )
    (net (code "25") (name "PCIE_A_RX3_N") (class "Default")
      (node (ref "J3") (pin "A29") (pinfunction "A29_A29") (pintype "passive"))
      (node (ref "JP1") (pin "A42") (pinfunction "A42_A42") (pintype "bidirectional"))
    )
    (net (code "26") (name "PCIE_A_RX3_P") (class "Default")
      (node (ref "J3") (pin "A30") (pinfunction "A30_A30") (pintype "passive"))
      (node (ref "JP1") (pin "A43") (pinfunction "A43_A43") (pintype "bidirectional"))
    )
    (net (code "27") (name "PCIE_A_TX0_N") (class "Default")
      (node (ref "J3") (pin "B14") (pinfunction "B14_B14") (pintype "passive"))
      (node (ref "JP1") (pin "B30") (pinfunction "B30_B30") (pintype "bidirectional"))
    )
    (net (code "28") (name "PCIE_A_TX0_P") (class "Default")
      (node (ref "J3") (pin "B15") (pinfunction "B15_B15") (pintype "passive"))
      (node (ref "JP1") (pin "B31") (pinfunction "B31_B31") (pintype "bidirectional"))
    )
    (net (code "29") (name "PCIE_A_TX1_N") (class "Default")
      (node (ref "J3") (pin "B19") (pinfunction "B19_B19") (pintype "passive"))
      (node (ref "JP1") (pin "B34") (pinfunction "B34_B34") (pintype "bidirectional"))
    )
    (net (code "30") (name "PCIE_A_TX1_P") (class "Default")
      (node (ref "J3") (pin "B20") (pinfunction "B20_B20") (pintype "passive"))
      (node (ref "JP1") (pin "B35") (pinfunction "B35_B35") (pintype "bidirectional"))
    )
    (net (code "31") (name "PCIE_A_TX2_N") (class "Default")
      (node (ref "J3") (pin "B24") (pinfunction "B24_B24") (pintype "passive"))
      (node (ref "JP1") (pin "B38") (pinfunction "B38_B38") (pintype "bidirectional"))
    )
    (net (code "32") (name "PCIE_A_TX2_P") (class "Default")
      (node (ref "J3") (pin "B23") (pinfunction "B23_B23") (pintype "passive"))
      (node (ref "JP1") (pin "B39") (pinfunction "B39_B39") (pintype "bidirectional"))
    )
    (net (code "33") (name "PCIE_A_TX3_N") (class "Default")
      (node (ref "J3") (pin "B27") (pinfunction "B27_B27") (pintype "passive"))
      (node (ref "JP1") (pin "B43") (pinfunction "B43_B43") (pintype "bidirectional"))
    )
    (net (code "34") (name "PCIE_A_TX3_P") (class "Default")
      (node (ref "J3") (pin "B28") (pinfunction "B28_B28") (pintype "passive"))
      (node (ref "JP1") (pin "B44") (pinfunction "B44_B44") (pintype "bidirectional"))
    )
    (net (code "35") (name "PCIE_B_CLKREQ") (class "Default")
      (node (ref "J2") (pin "52") (pinfunction "52_52") (pintype "passive"))
      (node (ref "R8") (pin "1") (pinfunction "1_1") (pintype "passive"))
      (node (ref "T1") (pin "1") (pinfunction "G_1") (pintype "passive"))
    )
    (net (code "36") (name "PCIE_B_CLK_N") (class "Default")
      (node (ref "IC1") (pin "14") (pinfunction "DIFF0_14") (pintype "output"))
      (node (ref "J2") (pin "53") (pinfunction "53_53") (pintype "passive"))
    )
    (net (code "37") (name "PCIE_B_CLK_P") (class "Default")
      (node (ref "IC1") (pin "13") (pinfunction "~{DIFF0}_13") (pintype "output"))
      (node (ref "J2") (pin "55") (pinfunction "55_55") (pintype "passive"))
    )
    (net (code "38") (name "PCIE_B_RX0_N") (class "Default")
      (node (ref "J2") (pin "43") (pinfunction "43_43") (pintype "passive"))
      (node (ref "JP1") (pin "A17") (pinfunction "A17_A17") (pintype "bidirectional"))
    )
    (net (code "39") (name "PCIE_B_RX0_P") (class "Default")
      (node (ref "J2") (pin "41") (pinfunction "41_41") (pintype "passive"))
      (node (ref "JP1") (pin "A18") (pinfunction "A18_A18") (pintype "bidirectional"))
    )
    (net (code "40") (name "PCIE_B_RX1_N") (class "Default")
      (node (ref "J2") (pin "31") (pinfunction "31_31") (pintype "passive"))
      (node (ref "JP1") (pin "A20") (pinfunction "A20_A20") (pintype "bidirectional"))
    )
    (net (code "41") (name "PCIE_B_RX1_P") (class "Default")
      (node (ref "J2") (pin "29") (pinfunction "29_29") (pintype "passive"))
      (node (ref "JP1") (pin "A21") (pinfunction "A21_A21") (pintype "bidirectional"))
    )
    (net (code "42") (name "PCIE_B_RX2_N") (class "Default")
      (node (ref "J2") (pin "19") (pinfunction "19_19") (pintype "passive"))
      (node (ref "JP1") (pin "A23") (pinfunction "A23_A23") (pintype "bidirectional"))
    )
    (net (code "43") (name "PCIE_B_RX2_P") (class "Default")
      (node (ref "J2") (pin "17") (pinfunction "17_17") (pintype "passive"))
      (node (ref "JP1") (pin "A24") (pinfunction "A24_A24") (pintype "bidirectional"))
    )
    (net (code "44") (name "PCIE_B_RX3_N") (class "Default")
      (node (ref "J2") (pin "5") (pinfunction "5_5") (pintype "passive"))
      (node (ref "JP1") (pin "A27") (pinfunction "A27_A27") (pintype "bidirectional"))
    )
    (net (code "45") (name "PCIE_B_RX3_P") (class "Default")
      (node (ref "J2") (pin "7") (pinfunction "7_7") (pintype "passive"))
      (node (ref "JP1") (pin "A26") (pinfunction "A26_A26") (pintype "bidirectional"))
    )
    (net (code "46") (name "PCIE_B_TX0_N") (class "Default")
      (node (ref "J2") (pin "49") (pinfunction "49_49") (pintype "passive"))
      (node (ref "JP1") (pin "B16") (pinfunction "B16_B16") (pintype "bidirectional"))
    )
    (net (code "47") (name "PCIE_B_TX0_P") (class "Default")
      (node (ref "J2") (pin "47") (pinfunction "47_47") (pintype "passive"))
      (node (ref "JP1") (pin "B17") (pinfunction "B17_B17") (pintype "bidirectional"))
    )
    (net (code "48") (name "PCIE_B_TX1_N") (class "Default")
      (node (ref "J2") (pin "37") (pinfunction "37_37") (pintype "passive"))
      (node (ref "JP1") (pin "B19") (pinfunction "B19_B19") (pintype "bidirectional"))
    )
    (net (code "49") (name "PCIE_B_TX1_P") (class "Default")
      (node (ref "J2") (pin "35") (pinfunction "35_35") (pintype "passive"))
      (node (ref "JP1") (pin "B20") (pinfunction "B20_B20") (pintype "bidirectional"))
    )
    (net (code "50") (name "PCIE_B_TX2_N") (class "Default")
      (node (ref "J2") (pin "25") (pinfunction "25_25") (pintype "passive"))
      (node (ref "JP1") (pin "B22") (pinfunction "B22_B22") (pintype "bidirectional"))
    )
    (net (code "51") (name "PCIE_B_TX2_P") (class "Default")
      (node (ref "J2") (pin "23") (pinfunction "23_23") (pintype "passive"))
      (node (ref "JP1") (pin "B23") (pinfunction "B23_B23") (pintype "bidirectional"))
    )
    (net (code "52") (name "PCIE_B_TX3_N") (class "Default")
      (node (ref "J2") (pin "11") (pinfunction "11_11") (pintype "passive"))
      (node (ref "JP1") (pin "B25") (pinfunction "B25_B25") (pintype "bidirectional"))
    )
    (net (code "53") (name "PCIE_B_TX3_P") (class "Default")
      (node (ref "J2") (pin "13") (pinfunction "13_13") (pintype "passive"))
      (node (ref "JP1") (pin "B26") (pinfunction "B26_B26") (pintype "bidirectional"))
    )
    (net (code "54") (name "PCIE_C_CLKREQ") (class "Default")
      (node (ref "J1") (pin "52") (pinfunction "52_52") (pintype "passive"))
      (node (ref "JP1") (pin "B14") (pinfunction "B14_B14") (pintype "bidirectional"))
    )
    (net (code "55") (name "PCIE_C_CLK_N") (class "Default")
      (node (ref "J1") (pin "53") (pinfunction "53_53") (pintype "passive"))
      (node (ref "JP1") (pin "A14") (pinfunction "A14_A14") (pintype "bidirectional"))
    )
    (net (code "56") (name "PCIE_C_CLK_P") (class "Default")
      (node (ref "J1") (pin "55") (pinfunction "55_55") (pintype "passive"))
      (node (ref "JP1") (pin "A15") (pinfunction "A15_A15") (pintype "bidirectional"))
    )
    (net (code "57") (name "PCIE_C_RX0_N") (class "Default")
      (node (ref "J1") (pin "41") (pinfunction "41_41") (pintype "passive"))
      (node (ref "JP1") (pin "B11") (pinfunction "B11_B11") (pintype "bidirectional"))
    )
    (net (code "58") (name "PCIE_C_RX0_P") (class "Default")
      (node (ref "J1") (pin "43") (pinfunction "43_43") (pintype "passive"))
      (node (ref "JP1") (pin "B12") (pinfunction "B12_B12") (pintype "bidirectional"))
    )
    (net (code "59") (name "PCIE_C_RX1_N") (class "Default")
      (node (ref "J1") (pin "31") (pinfunction "31_31") (pintype "passive"))
      (node (ref "JP1") (pin "A11") (pinfunction "A11_A11") (pintype "bidirectional"))
    )
    (net (code "60") (name "PCIE_C_RX1_P") (class "Default")
      (node (ref "J1") (pin "29") (pinfunction "29_29") (pintype "passive"))
      (node (ref "JP1") (pin "A12") (pinfunction "A12_A12") (pintype "bidirectional"))
    )
    (net (code "61") (name "PCIE_C_RX2_N") (class "Default")
      (node (ref "J1") (pin "17") (pinfunction "17_17") (pintype "passive"))
      (node (ref "JP1") (pin "A9") (pinfunction "A9_A9") (pintype "bidirectional"))
    )
    (net (code "62") (name "PCIE_C_RX2_P") (class "Default")
      (node (ref "J1") (pin "19") (pinfunction "19_19") (pintype "passive"))
      (node (ref "JP1") (pin "A8") (pinfunction "A8_A8") (pintype "bidirectional"))
    )
    (net (code "63") (name "PCIE_C_RX3_N") (class "Default")
      (node (ref "J1") (pin "7") (pinfunction "7_7") (pintype "passive"))
      (node (ref "JP1") (pin "B8") (pinfunction "B8_B8") (pintype "bidirectional"))
    )
    (net (code "64") (name "PCIE_C_RX3_P") (class "Default")
      (node (ref "J1") (pin "5") (pinfunction "5_5") (pintype "passive"))
      (node (ref "JP1") (pin "B9") (pinfunction "B9_B9") (pintype "bidirectional"))
    )
    (net (code "65") (name "PCIE_C_TX0_N") (class "Default")
      (node (ref "J1") (pin "49") (pinfunction "49_49") (pintype "passive"))
      (node (ref "JP1") (pin "B5") (pinfunction "B5_B5") (pintype "bidirectional"))
    )
    (net (code "66") (name "PCIE_C_TX0_P") (class "Default")
      (node (ref "J1") (pin "47") (pinfunction "47_47") (pintype "passive"))
      (node (ref "JP1") (pin "B6") (pinfunction "B6_B6") (pintype "bidirectional"))
    )
    (net (code "67") (name "PCIE_C_TX1_N") (class "Default")
      (node (ref "J1") (pin "37") (pinfunction "37_37") (pintype "passive"))
      (node (ref "JP1") (pin "A5") (pinfunction "A5_A5") (pintype "bidirectional"))
    )
    (net (code "68") (name "PCIE_C_TX1_P") (class "Default")
      (node (ref "J1") (pin "35") (pinfunction "35_35") (pintype "passive"))
      (node (ref "JP1") (pin "A6") (pinfunction "A6_A6") (pintype "bidirectional"))
    )
    (net (code "69") (name "PCIE_C_TX2_N") (class "Default")
      (node (ref "J1") (pin "25") (pinfunction "25_25") (pintype "passive"))
      (node (ref "JP1") (pin "B2") (pinfunction "B2_B2") (pintype "bidirectional"))
    )
    (net (code "70") (name "PCIE_C_TX2_P") (class "Default")
      (node (ref "J1") (pin "23") (pinfunction "23_23") (pintype "passive"))
      (node (ref "JP1") (pin "B3") (pinfunction "B3_B3") (pintype "bidirectional"))
    )
    (net (code "71") (name "PCIE_C_TX3_N") (class "Default")
      (node (ref "J1") (pin "13") (pinfunction "13_13") (pintype "passive"))
      (node (ref "JP1") (pin "A2") (pinfunction "A2_A2") (pintype "bidirectional"))
    )
    (net (code "72") (name "PCIE_C_TX3_P") (class "Default")
      (node (ref "J1") (pin "11") (pinfunction "11_11") (pintype "passive"))
      (node (ref "JP1") (pin "A3") (pinfunction "A3_A3") (pintype "bidirectional"))
    )
    (net (code "73") (name "SMBCLK") (class "Default")
      (node (ref "IC1") (pin "19") (pinfunction "SCLK_19") (pintype "input"))
      (node (ref "JP1") (pin "B53") (pinfunction "B53_B53") (pintype "bidirectional"))
    )
    (net (code "74") (name "SMBDAT") (class "Default")
      (node (ref "IC1") (pin "20") (pinfunction "SDATA_20") (pintype "bidirectional"))
      (node (ref "JP1") (pin "B52") (pinfunction "B52_B52") (pintype "bidirectional"))
    )
    (net (code "75") (name "VCC") (class "Default")
      (node (ref "C10") (pin "1") (pinfunction "1_1") (pintype "passive"))
      (node (ref "C11") (pin "1") (pinfunction "1_1") (pintype "passive"))
      (node (ref "C2") (pin "1") (pinfunction "1_1") (pintype "passive"))
      (node (ref "C3") (pin "1") (pinfunction "1_1") (pintype "passive"))
      (node (ref "C4") (pin "1") (pinfunction "1_1") (pintype "passive"))
      (node (ref "C5") (pin "1") (pinfunction "1_1") (pintype "passive"))
      (node (ref "J1") (pin "12") (pinfunction "12_12") (pintype "passive"))
      (node (ref "J1") (pin "14") (pinfunction "14_14") (pintype "passive"))
      (node (ref "J1") (pin "16") (pinfunction "16_16") (pintype "passive"))
      (node (ref "J1") (pin "18") (pinfunction "18_18") (pintype "passive"))
      (node (ref "J1") (pin "2") (pinfunction "2_2") (pintype "passive"))
      (node (ref "J1") (pin "4") (pinfunction "4_4") (pintype "passive"))
      (node (ref "J1") (pin "70") (pinfunction "70_70") (pintype "passive"))
      (node (ref "J1") (pin "72") (pinfunction "72_72") (pintype "passive"))
      (node (ref "J1") (pin "74") (pinfunction "74_74") (pintype "passive"))
      (node (ref "J2") (pin "12") (pinfunction "12_12") (pintype "passive"))
      (node (ref "J2") (pin "14") (pinfunction "14_14") (pintype "passive"))
      (node (ref "J2") (pin "16") (pinfunction "16_16") (pintype "passive"))
      (node (ref "J2") (pin "18") (pinfunction "18_18") (pintype "passive"))
      (node (ref "J2") (pin "2") (pinfunction "2_2") (pintype "passive"))
      (node (ref "J2") (pin "4") (pinfunction "4_4") (pintype "passive"))
      (node (ref "J2") (pin "70") (pinfunction "70_70") (pintype "passive"))
      (node (ref "J2") (pin "72") (pinfunction "72_72") (pintype "passive"))
      (node (ref "J2") (pin "74") (pinfunction "74_74") (pintype "passive"))
      (node (ref "L1") (pin "2") (pinfunction "2_2") (pintype "passive"))
      (node (ref "R5") (pin "2") (pinfunction "2_2") (pintype "passive"))
    )
    (net (code "76") (name "VCCINT") (class "Default")
      (node (ref "C13") (pin "1") (pinfunction "1_1") (pintype "passive"))
      (node (ref "J3") (pin "B10") (pinfunction "B10_B10") (pintype "passive"))
      (node (ref "JP1") (pin "A50") (pinfunction "A50_A50") (pintype "bidirectional"))
      (node (ref "JP1") (pin "B47") (pinfunction "B47_B47") (pintype "bidirectional"))
      (node (ref "R3") (pin "2") (pinfunction "2_2") (pintype "passive"))
      (node (ref "Y1") (pin "4") (pinfunction "VDD_4") (pintype "input"))
    )
    (net (code "77") (name "unconnected-(IC1-NC-Pad11)") (class "Default")
      (node (ref "IC1") (pin "11") (pinfunction "NC_11") (pintype "no_connect"))
    )
    (net (code "78") (name "unconnected-(IC1-NC_2-Pad2)") (class "Default")
      (node (ref "IC1") (pin "2") (pinfunction "NC_2_2") (pintype "no_connect"))
    )
    (net (code "79") (name "unconnected-(IC1-NC_3-Pad7)") (class "Default")
      (node (ref "IC1") (pin "7") (pinfunction "NC_3_7") (pintype "no_connect"))
    )
    (net (code "80") (name "unconnected-(IC1-NC_4-Pad8)") (class "Default")
      (node (ref "IC1") (pin "8") (pinfunction "NC_4_8") (pintype "no_connect"))
    )
    (net (code "81") (name "unconnected-(IC1-NC_5-Pad9)") (class "Default")
      (node (ref "IC1") (pin "9") (pinfunction "NC_5_9") (pintype "no_connect"))
    )
    (net (code "82") (name "unconnected-(IC1-NC_6-Pad10)") (class "Default")
      (node (ref "IC1") (pin "10") (pinfunction "NC_6_10") (pintype "no_connect"))
    )
    (net (code "83") (name "unconnected-(IC2-MODE-Pad12)") (class "Default")
      (node (ref "IC2") (pin "12") (pinfunction "MODE_12") (pintype "input"))
    )
    (net (code "84") (name "unconnected-(IC2-NC-Pad6)") (class "Default")
      (node (ref "IC2") (pin "6") (pinfunction "NC_6") (pintype "no_connect"))
    )
    (net (code "85") (name "unconnected-(IC2-SS-Pad5)") (class "Default")
      (node (ref "IC2") (pin "5") (pinfunction "SS_5") (pintype "output"))
    )
    (net (code "86") (name "unconnected-(J1-Pad6)") (class "Default")
      (node (ref "J1") (pin "6") (pinfunction "6_6") (pintype "passive"))
    )
    (net (code "87") (name "unconnected-(J1-Pad8)") (class "Default")
      (node (ref "J1") (pin "8") (pinfunction "8_8") (pintype "passive"))
    )
    (net (code "88") (name "unconnected-(J1-Pad10)") (class "Default")
      (node (ref "J1") (pin "10") (pinfunction "10_10") (pintype "passive"))
    )
    (net (code "89") (name "unconnected-(J1-Pad20)") (class "Default")
      (node (ref "J1") (pin "20") (pinfunction "20_20") (pintype "passive"))
    )
    (net (code "90") (name "unconnected-(J1-Pad22)") (class "Default")
      (node (ref "J1") (pin "22") (pinfunction "22_22") (pintype "passive"))
    )
    (net (code "91") (name "unconnected-(J1-Pad24)") (class "Default")
      (node (ref "J1") (pin "24") (pinfunction "24_24") (pintype "passive"))
    )
    (net (code "92") (name "unconnected-(J1-Pad26)") (class "Default")
      (node (ref "J1") (pin "26") (pinfunction "26_26") (pintype "passive"))
    )
    (net (code "93") (name "unconnected-(J1-Pad28)") (class "Default")
      (node (ref "J1") (pin "28") (pinfunction "28_28") (pintype "passive"))
    )
    (net (code "94") (name "unconnected-(J1-Pad30)") (class "Default")
      (node (ref "J1") (pin "30") (pinfunction "30_30") (pintype "passive"))
    )
    (net (code "95") (name "unconnected-(J1-Pad32)") (class "Default")
      (node (ref "J1") (pin "32") (pinfunction "32_32") (pintype "passive"))
    )
    (net (code "96") (name "unconnected-(J1-Pad34)") (class "Default")
      (node (ref "J1") (pin "34") (pinfunction "34_34") (pintype "passive"))
    )
    (net (code "97") (name "unconnected-(J1-Pad36)") (class "Default")
      (node (ref "J1") (pin "36") (pinfunction "36_36") (pintype "passive"))
    )
    (net (code "98") (name "unconnected-(J1-Pad38)") (class "Default")
      (node (ref "J1") (pin "38") (pinfunction "38_38") (pintype "passive"))
    )
    (net (code "99") (name "unconnected-(J1-Pad40)") (class "Default")
      (node (ref "J1") (pin "40") (pinfunction "40_40") (pintype "passive"))
    )
    (net (code "100") (name "unconnected-(J1-Pad42)") (class "Default")
      (node (ref "J1") (pin "42") (pinfunction "42_42") (pintype "passive"))
    )
    (net (code "101") (name "unconnected-(J1-Pad44)") (class "Default")
      (node (ref "J1") (pin "44") (pinfunction "44_44") (pintype "passive"))
    )
    (net (code "102") (name "unconnected-(J1-Pad46)") (class "Default")
      (node (ref "J1") (pin "46") (pinfunction "46_46") (pintype "passive"))
    )
    (net (code "103") (name "unconnected-(J1-Pad48)") (class "Default")
      (node (ref "J1") (pin "48") (pinfunction "48_48") (pintype "passive"))
    )
    (net (code "104") (name "unconnected-(J1-Pad56)") (class "Default")
      (node (ref "J1") (pin "56") (pinfunction "56_56") (pintype "passive"))
    )
    (net (code "105") (name "unconnected-(J1-Pad58)") (class "Default")
      (node (ref "J1") (pin "58") (pinfunction "58_58") (pintype "passive"))
    )
    (net (code "106") (name "unconnected-(J1-Pad67)") (class "Default")
      (node (ref "J1") (pin "67") (pinfunction "67_67") (pintype "passive"))
    )
    (net (code "107") (name "unconnected-(J1-Pad69)") (class "Default")
      (node (ref "J1") (pin "69") (pinfunction "69_69") (pintype "passive"))
    )
    (net (code "108") (name "unconnected-(J2-Pad6)") (class "Default")
      (node (ref "J2") (pin "6") (pinfunction "6_6") (pintype "passive"))
    )
    (net (code "109") (name "unconnected-(J2-Pad8)") (class "Default")
      (node (ref "J2") (pin "8") (pinfunction "8_8") (pintype "passive"))
    )
    (net (code "110") (name "unconnected-(J2-Pad10)") (class "Default")
      (node (ref "J2") (pin "10") (pinfunction "10_10") (pintype "passive"))
    )
    (net (code "111") (name "unconnected-(J2-Pad20)") (class "Default")
      (node (ref "J2") (pin "20") (pinfunction "20_20") (pintype "passive"))
    )
    (net (code "112") (name "unconnected-(J2-Pad22)") (class "Default")
      (node (ref "J2") (pin "22") (pinfunction "22_22") (pintype "passive"))
    )
    (net (code "113") (name "unconnected-(J2-Pad24)") (class "Default")
      (node (ref "J2") (pin "24") (pinfunction "24_24") (pintype "passive"))
    )
    (net (code "114") (name "unconnected-(J2-Pad26)") (class "Default")
      (node (ref "J2") (pin "26") (pinfunction "26_26") (pintype "passive"))
    )
    (net (code "115") (name "unconnected-(J2-Pad28)") (class "Default")
      (node (ref "J2") (pin "28") (pinfunction "28_28") (pintype "passive"))
    )
    (net (code "116") (name "unconnected-(J2-Pad30)") (class "Default")
      (node (ref "J2") (pin "30") (pinfunction "30_30") (pintype "passive"))
    )
    (net (code "117") (name "unconnected-(J2-Pad32)") (class "Default")
      (node (ref "J2") (pin "32") (pinfunction "32_32") (pintype "passive"))
    )
    (net (code "118") (name "unconnected-(J2-Pad34)") (class "Default")
      (node (ref "J2") (pin "34") (pinfunction "34_34") (pintype "passive"))
    )
    (net (code "119") (name "unconnected-(J2-Pad36)") (class "Default")
      (node (ref "J2") (pin "36") (pinfunction "36_36") (pintype "passive"))
    )
    (net (code "120") (name "unconnected-(J2-Pad38)") (class "Default")
      (node (ref "J2") (pin "38") (pinfunction "38_38") (pintype "passive"))
    )
    (net (code "121") (name "unconnected-(J2-Pad40)") (class "Default")
      (node (ref "J2") (pin "40") (pinfunction "40_40") (pintype "passive"))
    )
    (net (code "122") (name "unconnected-(J2-Pad42)") (class "Default")
      (node (ref "J2") (pin "42") (pinfunction "42_42") (pintype "passive"))
    )
    (net (code "123") (name "unconnected-(J2-Pad44)") (class "Default")
      (node (ref "J2") (pin "44") (pinfunction "44_44") (pintype "passive"))
    )
    (net (code "124") (name "unconnected-(J2-Pad46)") (class "Default")
      (node (ref "J2") (pin "46") (pinfunction "46_46") (pintype "passive"))
    )
    (net (code "125") (name "unconnected-(J2-Pad48)") (class "Default")
      (node (ref "J2") (pin "48") (pinfunction "48_48") (pintype "passive"))
    )
    (net (code "126") (name "unconnected-(J2-Pad56)") (class "Default")
      (node (ref "J2") (pin "56") (pinfunction "56_56") (pintype "passive"))
    )
    (net (code "127") (name "unconnected-(J2-Pad58)") (class "Default")
      (node (ref "J2") (pin "58") (pinfunction "58_58") (pintype "passive"))
    )
    (net (code "128") (name "unconnected-(J2-Pad67)") (class "Default")
      (node (ref "J2") (pin "67") (pinfunction "67_67") (pintype "passive"))
    )
    (net (code "129") (name "unconnected-(J2-Pad69)") (class "Default")
      (node (ref "J2") (pin "69") (pinfunction "69_69") (pintype "passive"))
    )
    (net (code "130") (name "unconnected-(J3-PadA5)") (class "Default")
      (node (ref "J3") (pin "A5") (pinfunction "A5_A5") (pintype "passive"))
    )
    (net (code "131") (name "unconnected-(J3-PadA6)") (class "Default")
      (node (ref "J3") (pin "A6") (pinfunction "A6_A6") (pintype "passive"))
    )
    (net (code "132") (name "unconnected-(J3-PadA7)") (class "Default")
      (node (ref "J3") (pin "A7") (pinfunction "A7_A7") (pintype "passive"))
    )
    (net (code "133") (name "unconnected-(J3-PadA8)") (class "Default")
      (node (ref "J3") (pin "A8") (pinfunction "A8_A8") (pintype "passive"))
    )
    (net (code "134") (name "unconnected-(J3-PadA19)") (class "Default")
      (node (ref "J3") (pin "A19") (pinfunction "A19_A19") (pintype "passive"))
    )
    (net (code "135") (name "unconnected-(J3-PadA32)") (class "Default")
      (node (ref "J3") (pin "A32") (pinfunction "A32_A32") (pintype "passive"))
    )
    (net (code "136") (name "unconnected-(J3-PadB5)") (class "Default")
      (node (ref "J3") (pin "B5") (pinfunction "B5_B5") (pintype "passive"))
    )
    (net (code "137") (name "unconnected-(J3-PadB6)") (class "Default")
      (node (ref "J3") (pin "B6") (pinfunction "B6_B6") (pintype "passive"))
    )
    (net (code "138") (name "unconnected-(J3-PadB9)") (class "Default")
      (node (ref "J3") (pin "B9") (pinfunction "B9_B9") (pintype "passive"))
    )
    (net (code "139") (name "unconnected-(J3-PadB12)") (class "Default")
      (node (ref "J3") (pin "B12") (pinfunction "B12_B12") (pintype "passive"))
    )
    (net (code "140") (name "unconnected-(J3-PadB17)") (class "Default")
      (node (ref "J3") (pin "B17") (pinfunction "B17_B17") (pintype "passive"))
    )
    (net (code "141") (name "unconnected-(J3-PadB30)") (class "Default")
      (node (ref "J3") (pin "B30") (pinfunction "B30_B30") (pintype "passive"))
    )
    (net (code "142") (name "unconnected-(J3-PadB31)") (class "Default")
      (node (ref "J3") (pin "B31") (pinfunction "B31_B31") (pintype "passive"))
    )
    (net (code "143") (name "unconnected-(J4-Pad3)") (class "Default")
      (node (ref "J4") (pin "3") (pinfunction "3_3") (pintype "passive"))
    )
    (net (code "144") (name "unconnected-(JP1-PadA1)") (class "Default")
      (node (ref "JP1") (pin "A1") (pinfunction "A1_A1") (pintype "bidirectional"))
    )
    (net (code "145") (name "unconnected-(JP1-PadA60)") (class "Default")
      (node (ref "JP1") (pin "A60") (pinfunction "A60_A60") (pintype "bidirectional"))
    )
    (net (code "146") (name "unconnected-(JP1-PadB1)") (class "Default")
      (node (ref "JP1") (pin "B1") (pinfunction "B1_B1") (pintype "bidirectional"))
    )
    (net (code "147") (name "unconnected-(JP1-PadB28)") (class "Default")
      (node (ref "JP1") (pin "B28") (pinfunction "B28_B28") (pintype "bidirectional"))
    )
  )
)
